# Adafruit_eInk_Breakout_Friend.net
KiCad netlist of a schematic drawn in EAGLE
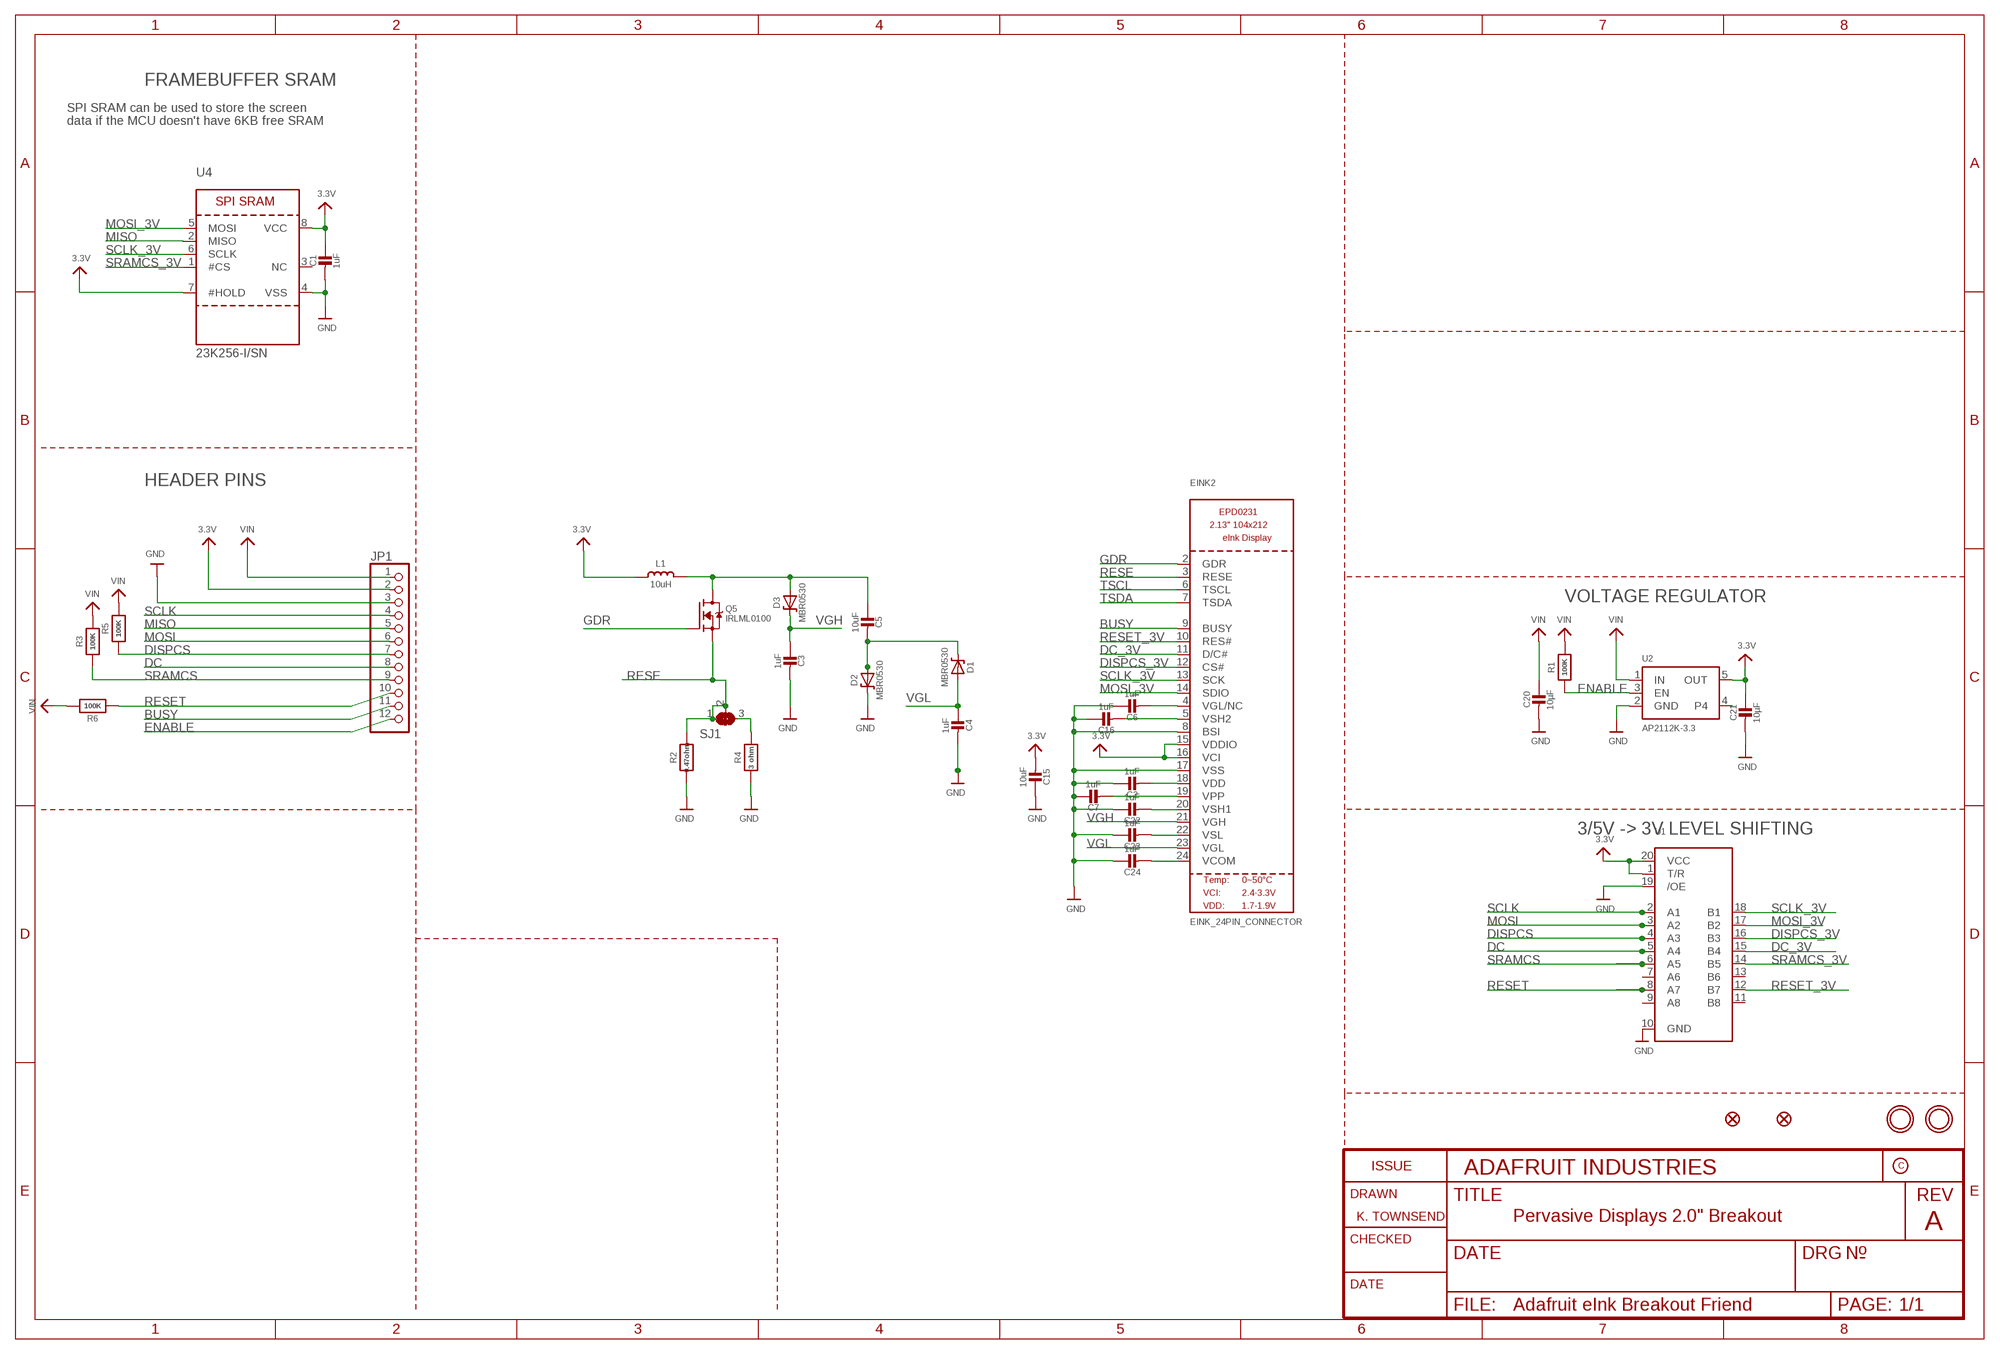
[diagram p0: schematic, sheet 1]

(export (version "E")
  (design (tool "Eeschema 10.0.6"))
  (components
    (comp (ref "C1")
      (value "1uF")
      (footprint "eagle-import:0805_10MGAP")
      (libsource (lib "eagle-import") (part "CAP_CERAMIC0805_10MGAP"))
    )
    (comp (ref "C2")
      (value "1uF")
      (footprint "eagle-import:0805-NO")
      (libsource (lib "eagle-import") (part "CAP_CERAMIC0805-NOOUTLINE"))
    )
    (comp (ref "C3")
      (value "1uF")
      (footprint "eagle-import:0805-NO")
      (libsource (lib "eagle-import") (part "CAP_CERAMIC0805-NOOUTLINE"))
    )
    (comp (ref "C4")
      (value "1uF")
      (footprint "eagle-import:0805-NO")
      (libsource (lib "eagle-import") (part "CAP_CERAMIC0805-NOOUTLINE"))
    )
    (comp (ref "C5")
      (value "10uF")
      (footprint "eagle-import:0805-NO")
      (libsource (lib "eagle-import") (part "CAP_CERAMIC0805-NOOUTLINE"))
    )
    (comp (ref "C6")
      (value "1uF")
      (footprint "eagle-import:0805-NO")
      (libsource (lib "eagle-import") (part "CAP_CERAMIC0805-NOOUTLINE"))
    )
    (comp (ref "C7")
      (value "1uF")
      (footprint "eagle-import:0805-NO")
      (libsource (lib "eagle-import") (part "CAP_CERAMIC0805-NOOUTLINE"))
    )
    (comp (ref "C15")
      (value "10uF")
      (footprint "eagle-import:0805-NO")
      (libsource (lib "eagle-import") (part "CAP_CERAMIC0805-NOOUTLINE"))
    )
    (comp (ref "C16")
      (value "1uF")
      (footprint "eagle-import:0805-NO")
      (libsource (lib "eagle-import") (part "CAP_CERAMIC0805-NOOUTLINE"))
    )
    (comp (ref "C20")
      (value "10µF")
      (footprint "eagle-import:0805-NO")
      (libsource (lib "eagle-import") (part "CAP_CERAMIC0805-NOOUTLINE"))
    )
    (comp (ref "C21")
      (value "10µF")
      (footprint "eagle-import:0805-NO")
      (libsource (lib "eagle-import") (part "CAP_CERAMIC0805-NOOUTLINE"))
    )
    (comp (ref "C22")
      (value "1uF")
      (footprint "eagle-import:0805-NO")
      (libsource (lib "eagle-import") (part "CAP_CERAMIC0805-NOOUTLINE"))
    )
    (comp (ref "C23")
      (value "1uF")
      (footprint "eagle-import:0805-NO")
      (libsource (lib "eagle-import") (part "CAP_CERAMIC0805-NOOUTLINE"))
    )
    (comp (ref "C24")
      (value "1uF")
      (footprint "eagle-import:0805-NO")
      (libsource (lib "eagle-import") (part "CAP_CERAMIC0805-NOOUTLINE"))
    )
    (comp (ref "D1")
      (value "MBR0530")
      (footprint "eagle-import:SOD-123")
      (libsource (lib "eagle-import") (part "DIODE-SCHOTTKYSOD-123"))
    )
    (comp (ref "D2")
      (value "MBR0530")
      (footprint "eagle-import:SOD-123")
      (libsource (lib "eagle-import") (part "DIODE-SCHOTTKYSOD-123"))
    )
    (comp (ref "D3")
      (value "MBR0530")
      (footprint "eagle-import:SOD-123")
      (libsource (lib "eagle-import") (part "DIODE-SCHOTTKYSOD-123"))
    )
    (comp (ref "EINK2")
      (value "EINK_24PIN_CONNECTOR")
      (footprint "eagle-import:EINK_24PIN")
      (libsource (lib "eagle-import") (part "EINK_24PIN_CONNECTOR"))
    )
    (comp (ref "FID2")
      (value "FIDUCIAL_1MM")
      (footprint "eagle-import:FIDUCIAL_1MM")
      (libsource (lib "eagle-import") (part "FIDUCIAL_1MM"))
    )
    (comp (ref "FID3")
      (value "FIDUCIAL_1MM")
      (footprint "eagle-import:FIDUCIAL_1MM")
      (libsource (lib "eagle-import") (part "FIDUCIAL_1MM"))
    )
    (comp (ref "JP1")
      (value "HEADER-1X1276MIL")
      (footprint "eagle-import:1X12_ROUND_76MIL")
      (libsource (lib "eagle-import") (part "HEADER-1X1276MIL"))
    )
    (comp (ref "L1")
      (value "10uH")
      (footprint "eagle-import:INDUCTOR_4X4MM_NR401")
      (libsource (lib "eagle-import") (part "INDUCTORNR401"))
    )
    (comp (ref "Q5")
      (value "IRLML0100")
      (footprint "eagle-import:SOT23-3")
      (libsource (lib "eagle-import") (part "IRLML2060TRPBF"))
    )
    (comp (ref "R1")
      (value "100K")
      (footprint "eagle-import:0603-NO")
      (libsource (lib "eagle-import") (part "RESISTOR_0603_NOOUT"))
    )
    (comp (ref "R2")
      (value "0.47ohm")
      (footprint "eagle-import:0805-NO")
      (libsource (lib "eagle-import") (part "RESISTOR0805_NOOUTLINE"))
    )
    (comp (ref "R3")
      (value "100K")
      (footprint "eagle-import:0603-NO")
      (libsource (lib "eagle-import") (part "RESISTOR_0603_NOOUT"))
    )
    (comp (ref "R4")
      (value "3 ohm")
      (footprint "eagle-import:0805-NO")
      (libsource (lib "eagle-import") (part "RESISTOR0805_NOOUTLINE"))
    )
    (comp (ref "R5")
      (value "100K")
      (footprint "eagle-import:0603-NO")
      (libsource (lib "eagle-import") (part "RESISTOR_0603_NOOUT"))
    )
    (comp (ref "R6")
      (value "100K")
      (footprint "eagle-import:0603-NO")
      (libsource (lib "eagle-import") (part "RESISTOR_0603_NOOUT"))
    )
    (comp (ref "SJ1")
      (value "SOLDERJUMPER_2WAY")
      (footprint "eagle-import:SOLDERJUMPER_2WAY_OPEN_NOPASTE")
      (libsource (lib "eagle-import") (part "SOLDERJUMPER_2WAY"))
    )
    (comp (ref "U$3")
      (value "MOUNTINGHOLE2.5")
      (footprint "eagle-import:MOUNTINGHOLE_2.5_PLATED")
      (libsource (lib "eagle-import") (part "MOUNTINGHOLE2.5"))
    )
    (comp (ref "U$4")
      (value "MOUNTINGHOLE2.5")
      (footprint "eagle-import:MOUNTINGHOLE_2.5_PLATED")
      (libsource (lib "eagle-import") (part "MOUNTINGHOLE2.5"))
    )
    (comp (ref "U1")
      (value "74LCX245")
      (footprint "eagle-import:TSSOP20")
      (libsource (lib "eagle-import") (part "74LCX245"))
    )
    (comp (ref "U2")
      (value "AP2112K-3.3")
      (footprint "eagle-import:SOT23-5")
      (libsource (lib "eagle-import") (part "VREG_SOT23-5"))
    )
    (comp (ref "U4")
      (value "23K256-I/SN")
      (footprint "eagle-import:SOIC8_150MIL")
      (libsource (lib "eagle-import") (part "SRAM_SPI_SOIC8"))
    )
  )
  (nets
    (net (code "1") (name "/BUSY") (class "Default")
      (node (ref "EINK2") (pin "9") (pinfunction "BUSY_9") (pintype "output"))
      (node (ref "JP1") (pin "11") (pinfunction "11_11") (pintype "passive"))
    )
    (net (code "2") (name "/DC") (class "Default")
      (node (ref "JP1") (pin "8") (pinfunction "8_8") (pintype "passive"))
      (node (ref "U1") (pin "5") (pinfunction "A4_5") (pintype "bidirectional"))
    )
    (net (code "3") (name "/DC_3V") (class "Default")
      (node (ref "EINK2") (pin "11") (pinfunction "D/C#_11") (pintype "input"))
      (node (ref "U1") (pin "15") (pinfunction "B4_15") (pintype "bidirectional"))
    )
    (net (code "4") (name "/DISPCS") (class "Default")
      (node (ref "JP1") (pin "7") (pinfunction "7_7") (pintype "passive"))
      (node (ref "R5") (pin "1") (pinfunction "1_1") (pintype "passive"))
      (node (ref "U1") (pin "4") (pinfunction "A3_4") (pintype "bidirectional"))
    )
    (net (code "5") (name "/DISPCS_3V") (class "Default")
      (node (ref "EINK2") (pin "12") (pinfunction "CS#_12") (pintype "input"))
      (node (ref "U1") (pin "16") (pinfunction "B3_16") (pintype "bidirectional"))
    )
    (net (code "6") (name "/ENABLE") (class "Default")
      (node (ref "JP1") (pin "12") (pinfunction "12_12") (pintype "passive"))
      (node (ref "R1") (pin "1") (pinfunction "1_1") (pintype "passive"))
      (node (ref "U2") (pin "3") (pinfunction "EN_3") (pintype "input"))
    )
    (net (code "7") (name "/GDR") (class "Default")
      (node (ref "EINK2") (pin "2") (pinfunction "GDR_2") (pintype "output"))
      (node (ref "Q5") (pin "1") (pinfunction "G_1") (pintype "bidirectional"))
    )
    (net (code "8") (name "/MISO") (class "Default")
      (node (ref "JP1") (pin "5") (pinfunction "5_5") (pintype "passive"))
      (node (ref "U4") (pin "2") (pinfunction "MISO_2") (pintype "output"))
    )
    (net (code "9") (name "/MOSI") (class "Default")
      (node (ref "JP1") (pin "6") (pinfunction "6_6") (pintype "passive"))
      (node (ref "U1") (pin "3") (pinfunction "A2_3") (pintype "bidirectional"))
    )
    (net (code "10") (name "/MOSI_3V") (class "Default")
      (node (ref "EINK2") (pin "14") (pinfunction "SDIO_14") (pintype "bidirectional"))
      (node (ref "U1") (pin "17") (pinfunction "B2_17") (pintype "bidirectional"))
      (node (ref "U4") (pin "5") (pinfunction "MOSI_5") (pintype "input"))
    )
    (net (code "11") (name "/RESE") (class "Default")
      (node (ref "EINK2") (pin "3") (pinfunction "RESE_3") (pintype "input"))
      (node (ref "Q5") (pin "2") (pinfunction "S_2") (pintype "bidirectional"))
      (node (ref "R2") (pin "1") (pinfunction "1_1") (pintype "passive"))
      (node (ref "SJ1") (pin "1") (pinfunction "1_1") (pintype "passive"))
      (node (ref "SJ1") (pin "2") (pinfunction "2_2") (pintype "passive"))
    )
    (net (code "12") (name "/RESET") (class "Default")
      (node (ref "JP1") (pin "10") (pinfunction "10_10") (pintype "passive"))
      (node (ref "R6") (pin "1") (pinfunction "1_1") (pintype "passive"))
      (node (ref "U1") (pin "8") (pinfunction "A7_8") (pintype "bidirectional"))
    )
    (net (code "13") (name "/RESET_3V") (class "Default")
      (node (ref "EINK2") (pin "10") (pinfunction "RES#_10") (pintype "input"))
      (node (ref "U1") (pin "12") (pinfunction "B7_12") (pintype "bidirectional"))
    )
    (net (code "14") (name "/SCLK") (class "Default")
      (node (ref "JP1") (pin "4") (pinfunction "4_4") (pintype "passive"))
      (node (ref "U1") (pin "2") (pinfunction "A1_2") (pintype "bidirectional"))
    )
    (net (code "15") (name "/SCLK_3V") (class "Default")
      (node (ref "EINK2") (pin "13") (pinfunction "SCK_13") (pintype "bidirectional"))
      (node (ref "U1") (pin "18") (pinfunction "B1_18") (pintype "bidirectional"))
      (node (ref "U4") (pin "6") (pinfunction "SCLK_6") (pintype "input"))
    )
    (net (code "16") (name "/SRAMCS") (class "Default")
      (node (ref "JP1") (pin "9") (pinfunction "9_9") (pintype "passive"))
      (node (ref "R3") (pin "1") (pinfunction "1_1") (pintype "passive"))
      (node (ref "U1") (pin "6") (pinfunction "A5_6") (pintype "bidirectional"))
    )
    (net (code "17") (name "/SRAMCS_3V") (class "Default")
      (node (ref "U1") (pin "14") (pinfunction "B5_14") (pintype "bidirectional"))
      (node (ref "U4") (pin "1") (pinfunction "#CS_1") (pintype "input"))
    )
    (net (code "18") (name "/TSCL") (class "Default")
      (node (ref "EINK2") (pin "6") (pinfunction "TSCL_6") (pintype "output"))
    )
    (net (code "19") (name "/TSDA") (class "Default")
      (node (ref "EINK2") (pin "7") (pinfunction "TSDA_7") (pintype "bidirectional"))
    )
    (net (code "20") (name "/VGH") (class "Default")
      (node (ref "C3") (pin "1") (pinfunction "1_1") (pintype "passive"))
      (node (ref "D3") (pin "C") (pinfunction "C_C") (pintype "passive"))
      (node (ref "EINK2") (pin "21") (pinfunction "VGH_21") (pintype "passive"))
    )
    (net (code "21") (name "/VGL") (class "Default")
      (node (ref "C4") (pin "1") (pinfunction "1_1") (pintype "passive"))
      (node (ref "D1") (pin "A") (pinfunction "A_A") (pintype "passive"))
      (node (ref "EINK2") (pin "23") (pinfunction "VGL_23") (pintype "passive"))
    )
    (net (code "22") (name "3.3V") (class "Default")
      (node (ref "C1") (pin "1") (pinfunction "1_1") (pintype "passive"))
      (node (ref "C15") (pin "2") (pinfunction "2_2") (pintype "passive"))
      (node (ref "C21") (pin "1") (pinfunction "1_1") (pintype "passive"))
      (node (ref "EINK2") (pin "15") (pinfunction "VDDIO_15") (pintype "power_in"))
      (node (ref "EINK2") (pin "16") (pinfunction "VCI_16") (pintype "power_in"))
      (node (ref "JP1") (pin "2") (pinfunction "2_2") (pintype "passive"))
      (node (ref "L1") (pin "P$2") (pinfunction "2_P$2") (pintype "passive"))
      (node (ref "U1") (pin "1") (pinfunction "T/R_1") (pintype "bidirectional"))
      (node (ref "U1") (pin "20") (pinfunction "VCC_20") (pintype "bidirectional"))
      (node (ref "U2") (pin "5") (pinfunction "OUT_5") (pintype "power_in"))
      (node (ref "U4") (pin "7") (pinfunction "#HOLD_7") (pintype "input"))
      (node (ref "U4") (pin "8") (pinfunction "VCC_8") (pintype "power_in"))
    )
    (net (code "23") (name "GND") (class "Default")
      (node (ref "C1") (pin "2") (pinfunction "2_2") (pintype "passive"))
      (node (ref "C15") (pin "1") (pinfunction "1_1") (pintype "passive"))
      (node (ref "C16") (pin "1") (pinfunction "1_1") (pintype "passive"))
      (node (ref "C2") (pin "1") (pinfunction "1_1") (pintype "passive"))
      (node (ref "C20") (pin "2") (pinfunction "2_2") (pintype "passive"))
      (node (ref "C21") (pin "2") (pinfunction "2_2") (pintype "passive"))
      (node (ref "C22") (pin "1") (pinfunction "1_1") (pintype "passive"))
      (node (ref "C23") (pin "1") (pinfunction "1_1") (pintype "passive"))
      (node (ref "C24") (pin "1") (pinfunction "1_1") (pintype "passive"))
      (node (ref "C3") (pin "2") (pinfunction "2_2") (pintype "passive"))
      (node (ref "C4") (pin "2") (pinfunction "2_2") (pintype "passive"))
      (node (ref "C6") (pin "1") (pinfunction "1_1") (pintype "passive"))
      (node (ref "C7") (pin "1") (pinfunction "1_1") (pintype "passive"))
      (node (ref "D2") (pin "C") (pinfunction "C_C") (pintype "passive"))
      (node (ref "EINK2") (pin "17") (pinfunction "VSS_17") (pintype "power_in"))
      (node (ref "EINK2") (pin "8") (pinfunction "BSI_8") (pintype "input"))
      (node (ref "JP1") (pin "3") (pinfunction "3_3") (pintype "passive"))
      (node (ref "R2") (pin "2") (pinfunction "2_2") (pintype "passive"))
      (node (ref "R4") (pin "2") (pinfunction "2_2") (pintype "passive"))
      (node (ref "U1") (pin "10") (pinfunction "GND_10") (pintype "bidirectional"))
      (node (ref "U1") (pin "19") (pinfunction "/OE_19") (pintype "bidirectional"))
      (node (ref "U2") (pin "2") (pinfunction "GND_2") (pintype "power_in"))
      (node (ref "U4") (pin "4") (pinfunction "VSS_4") (pintype "power_in"))
    )
    (net (code "24") (name "Net-(C5-Pad2)") (class "Default")
      (node (ref "C5") (pin "2") (pinfunction "2_2") (pintype "passive"))
      (node (ref "D1") (pin "C") (pinfunction "C_C") (pintype "passive"))
      (node (ref "D2") (pin "A") (pinfunction "A_A") (pintype "passive"))
    )
    (net (code "25") (name "Net-(EINK2-VCOM)") (class "Default")
      (node (ref "C24") (pin "2") (pinfunction "2_2") (pintype "passive"))
      (node (ref "EINK2") (pin "24") (pinfunction "VCOM_24") (pintype "passive"))
    )
    (net (code "26") (name "Net-(EINK2-VDD)") (class "Default")
      (node (ref "C2") (pin "2") (pinfunction "2_2") (pintype "passive"))
      (node (ref "EINK2") (pin "18") (pinfunction "VDD_18") (pintype "passive"))
    )
    (net (code "27") (name "Net-(EINK2-VGL{slash}NC)") (class "Default")
      (node (ref "C6") (pin "2") (pinfunction "2_2") (pintype "passive"))
      (node (ref "EINK2") (pin "4") (pinfunction "VGL/NC_4") (pintype "bidirectional"))
    )
    (net (code "28") (name "Net-(EINK2-VPP)") (class "Default")
      (node (ref "C7") (pin "2") (pinfunction "2_2") (pintype "passive"))
      (node (ref "EINK2") (pin "19") (pinfunction "VPP_19") (pintype "passive"))
    )
    (net (code "29") (name "Net-(EINK2-VSH1)") (class "Default")
      (node (ref "C22") (pin "2") (pinfunction "2_2") (pintype "passive"))
      (node (ref "EINK2") (pin "20") (pinfunction "VSH1_20") (pintype "passive"))
    )
    (net (code "30") (name "Net-(EINK2-VSH2)") (class "Default")
      (node (ref "C16") (pin "2") (pinfunction "2_2") (pintype "passive"))
      (node (ref "EINK2") (pin "5") (pinfunction "VSH2_5") (pintype "passive"))
    )
    (net (code "31") (name "Net-(EINK2-VSL)") (class "Default")
      (node (ref "C23") (pin "2") (pinfunction "2_2") (pintype "passive"))
      (node (ref "EINK2") (pin "22") (pinfunction "VSL_22") (pintype "passive"))
    )
    (net (code "32") (name "Net-(L1-1)") (class "Default")
      (node (ref "C5") (pin "1") (pinfunction "1_1") (pintype "passive"))
      (node (ref "D3") (pin "A") (pinfunction "A_A") (pintype "passive"))
      (node (ref "L1") (pin "P$1") (pinfunction "1_P$1") (pintype "passive"))
      (node (ref "Q5") (pin "3") (pinfunction "D_3") (pintype "bidirectional"))
    )
    (net (code "33") (name "Net-(R4-Pad1)") (class "Default")
      (node (ref "R4") (pin "1") (pinfunction "1_1") (pintype "passive"))
      (node (ref "SJ1") (pin "3") (pinfunction "3_3") (pintype "passive"))
    )
    (net (code "34") (name "VIN") (class "Default")
      (node (ref "C20") (pin "1") (pinfunction "1_1") (pintype "passive"))
      (node (ref "JP1") (pin "1") (pinfunction "1_1") (pintype "passive"))
      (node (ref "R1") (pin "2") (pinfunction "2_2") (pintype "passive"))
      (node (ref "R3") (pin "2") (pinfunction "2_2") (pintype "passive"))
      (node (ref "R5") (pin "2") (pinfunction "2_2") (pintype "passive"))
      (node (ref "R6") (pin "2") (pinfunction "2_2") (pintype "passive"))
      (node (ref "U2") (pin "1") (pinfunction "IN_1") (pintype "power_in"))
    )
    (net (code "35") (name "unconnected-(U1-A6-Pad7)") (class "Default")
      (node (ref "U1") (pin "7") (pinfunction "A6_7") (pintype "bidirectional"))
    )
    (net (code "36") (name "unconnected-(U1-A8-Pad9)") (class "Default")
      (node (ref "U1") (pin "9") (pinfunction "A8_9") (pintype "bidirectional"))
    )
    (net (code "37") (name "unconnected-(U1-B6-Pad13)") (class "Default")
      (node (ref "U1") (pin "13") (pinfunction "B6_13") (pintype "bidirectional"))
    )
    (net (code "38") (name "unconnected-(U1-B8-Pad11)") (class "Default")
      (node (ref "U1") (pin "11") (pinfunction "B8_11") (pintype "bidirectional"))
    )
    (net (code "39") (name "unconnected-(U2-P4-Pad4)") (class "Default")
      (node (ref "U2") (pin "4") (pinfunction "P4_4") (pintype "bidirectional"))
    )
    (net (code "40") (name "unconnected-(U4-NC-Pad3)") (class "Default")
      (node (ref "U4") (pin "3") (pinfunction "NC_3") (pintype "no_connect"))
    )
  )
)
